# motor.net
KiCad netlist of a schematic drawn in EAGLE
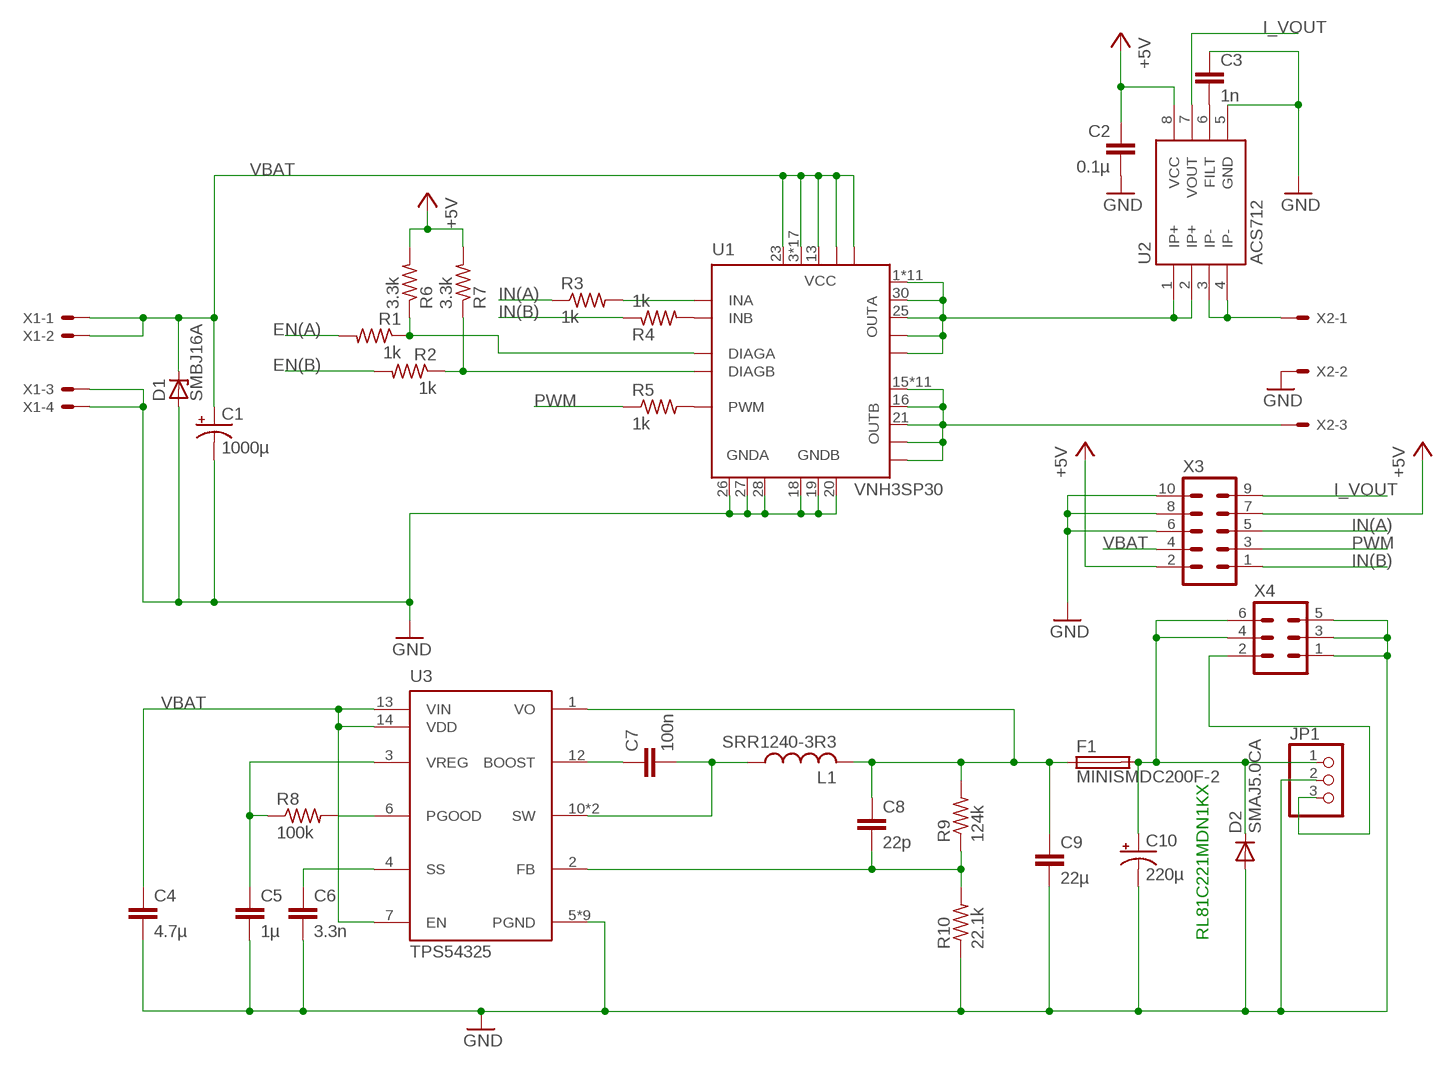
[diagram p0: schematic, sheet 1]

(export (version "E")
  (design (tool "Eeschema 10.0.6"))
  (components
    (comp (ref "C1")
      (value "1000µ")
      (footprint "eagle-import:E5-13")
      (libsource (lib "eagle-import") (part "CPOL-USE5-13"))
    )
    (comp (ref "C2")
      (value "0.1µ")
      (footprint "eagle-import:C0805")
      (libsource (lib "eagle-import") (part "C-EUC0805"))
    )
    (comp (ref "C3")
      (value "1n")
      (footprint "eagle-import:C0805")
      (libsource (lib "eagle-import") (part "C-EUC0805"))
    )
    (comp (ref "C4")
      (value "4.7µ")
      (footprint "eagle-import:C1206")
      (libsource (lib "eagle-import") (part "C-EUC1206"))
    )
    (comp (ref "C5")
      (value "1µ")
      (footprint "eagle-import:C0805")
      (libsource (lib "eagle-import") (part "C-EUC0805"))
    )
    (comp (ref "C6")
      (value "3.3n")
      (footprint "eagle-import:C0805")
      (libsource (lib "eagle-import") (part "C-EUC0805"))
    )
    (comp (ref "C7")
      (value "100n")
      (footprint "eagle-import:C0805")
      (libsource (lib "eagle-import") (part "C-EUC0805"))
    )
    (comp (ref "C8")
      (value "22p")
      (footprint "eagle-import:C0805")
      (libsource (lib "eagle-import") (part "C-EUC0805"))
    )
    (comp (ref "C9")
      (value "22µ")
      (footprint "eagle-import:C3225")
      (libsource (lib "eagle-import") (part "C-EUC3225"))
    )
    (comp (ref "C10")
      (value "220µ")
      (footprint "eagle-import:E3,5-8")
      (libsource (lib "eagle-import") (part "CPOL-USE3.5-8"))
    )
    (comp (ref "D1")
      (value "SMBJ16A")
      (footprint "eagle-import:SMB")
      (libsource (lib "eagle-import") (part "ZENER-DIODESMB"))
    )
    (comp (ref "D2")
      (value "SMAJ5.0CA")
      (footprint "eagle-import:DO-214AC")
      (libsource (lib "eagle-import") (part "DIODE-DO-214AC"))
    )
    (comp (ref "F1")
      (value "MINISMDC200F-2")
      (footprint "eagle-import:MINISMDC200F")
      (libsource (lib "eagle-import") (part "FUSEMINISMDC200F"))
    )
    (comp (ref "JP1")
      (value "PINHD-1X3")
      (footprint "eagle-import:1X03")
      (libsource (lib "eagle-import") (part "PINHD-1X3"))
    )
    (comp (ref "L1")
      (value "SRR1240-3R3")
      (footprint "eagle-import:HCM1103")
      (libsource (lib "eagle-import") (part "L-USHCM1103"))
    )
    (comp (ref "R1")
      (value "1k")
      (footprint "eagle-import:R0805")
      (libsource (lib "eagle-import") (part "R-US_R0805"))
    )
    (comp (ref "R2")
      (value "1k")
      (footprint "eagle-import:R0805")
      (libsource (lib "eagle-import") (part "R-US_R0805"))
    )
    (comp (ref "R3")
      (value "1k")
      (footprint "eagle-import:R0805")
      (libsource (lib "eagle-import") (part "R-US_R0805"))
    )
    (comp (ref "R4")
      (value "1k")
      (footprint "eagle-import:R0805")
      (libsource (lib "eagle-import") (part "R-US_R0805"))
    )
    (comp (ref "R5")
      (value "1k")
      (footprint "eagle-import:R0805")
      (libsource (lib "eagle-import") (part "R-US_R0805"))
    )
    (comp (ref "R6")
      (value "3.3k")
      (footprint "eagle-import:R0805")
      (libsource (lib "eagle-import") (part "R-US_R0805"))
    )
    (comp (ref "R7")
      (value "3.3k")
      (footprint "eagle-import:R0805")
      (libsource (lib "eagle-import") (part "R-US_R0805"))
    )
    (comp (ref "R8")
      (value "100k")
      (footprint "eagle-import:R0805")
      (libsource (lib "eagle-import") (part "R-US_R0805"))
    )
    (comp (ref "R9")
      (value "124k")
      (footprint "eagle-import:R0805")
      (libsource (lib "eagle-import") (part "R-US_R0805"))
    )
    (comp (ref "R10")
      (value "22.1k")
      (footprint "eagle-import:R0805")
      (libsource (lib "eagle-import") (part "R-US_R0805"))
    )
    (comp (ref "U1")
      (value "VNH3SP30")
      (footprint "eagle-import:MULTIPOWERSO-30")
      (fields (field (name "MPN") "VNH3SP30-E"))
      (libsource (lib "eagle-import") (part "VNH3SP30"))
    )
    (comp (ref "U2")
      (value "ACS712")
      (footprint "eagle-import:SO08")
      (libsource (lib "eagle-import") (part "ACS712"))
    )
    (comp (ref "U3")
      (value "TPS54325")
      (footprint "eagle-import:HTSSOP14PWP")
      (libsource (lib "eagle-import") (part "TPS54325"))
    )
    (comp (ref "X1")
      (value "KK-156-4")
      (footprint "eagle-import:KK-156-4")
      (libsource (lib "eagle-import") (part "KK-156-4"))
    )
    (comp (ref "X2")
      (value "KK-156-3")
      (footprint "eagle-import:KK-156-3")
      (libsource (lib "eagle-import") (part "KK-156-3"))
    )
    (comp (ref "X3")
      (value "ML10")
      (footprint "eagle-import:ML10")
      (libsource (lib "eagle-import") (part "ML10"))
    )
    (comp (ref "X4")
      (value "ML6")
      (footprint "eagle-import:ML6")
      (libsource (lib "eagle-import") (part "ML6"))
    )
  )
  (nets
    (net (code "1") (name "+5V") (class "Default")
      (node (ref "C2") (pin "1") (pinfunction "1_1") (pintype "passive"))
      (node (ref "R6") (pin "2") (pinfunction "2_2") (pintype "passive"))
      (node (ref "R7") (pin "2") (pinfunction "2_2") (pintype "passive"))
      (node (ref "U2") (pin "8") (pinfunction "VCC_8") (pintype "bidirectional"))
      (node (ref "X3") (pin "2") (pinfunction "2_2") (pintype "passive"))
      (node (ref "X3") (pin "7") (pinfunction "7_7") (pintype "passive"))
    )
    (net (code "2") (name "/EN(A)") (class "Default")
      (node (ref "R1") (pin "2") (pinfunction "2_2") (pintype "passive"))
    )
    (net (code "3") (name "/EN(B)") (class "Default")
      (node (ref "R2") (pin "2") (pinfunction "2_2") (pintype "passive"))
    )
    (net (code "4") (name "/IN(A)") (class "Default")
      (node (ref "R3") (pin "1") (pinfunction "1_1") (pintype "passive"))
      (node (ref "X3") (pin "5") (pinfunction "5_5") (pintype "passive"))
    )
    (net (code "5") (name "/IN(B)") (class "Default")
      (node (ref "R4") (pin "1") (pinfunction "1_1") (pintype "passive"))
      (node (ref "X3") (pin "1") (pinfunction "1_1") (pintype "passive"))
    )
    (net (code "6") (name "/I_VOUT") (class "Default")
      (node (ref "U2") (pin "7") (pinfunction "VOUT_7") (pintype "bidirectional"))
      (node (ref "X3") (pin "9") (pinfunction "9_9") (pintype "passive"))
    )
    (net (code "7") (name "/PWM") (class "Default")
      (node (ref "R5") (pin "1") (pinfunction "1_1") (pintype "passive"))
      (node (ref "X3") (pin "3") (pinfunction "3_3") (pintype "passive"))
    )
    (net (code "8") (name "/VBAT") (class "Default")
      (node (ref "C1") (pin "+") (pinfunction "+_+") (pintype "passive"))
      (node (ref "C4") (pin "1") (pinfunction "1_1") (pintype "passive"))
      (node (ref "D1") (pin "C") (pinfunction "C_C") (pintype "passive"))
      (node (ref "U1") (pin "13") (pinfunction "VCC_13") (pintype "power_in"))
      (node (ref "U1") (pin "23") (pinfunction "VCC_23") (pintype "power_in"))
      (node (ref "U1") (pin "3") (pinfunction "VCC_3") (pintype "power_in"))
      (node (ref "U1") (pin "VCC") (pinfunction "VCC_VCC") (pintype "power_in"))
      (node (ref "U1") (pin "VCC1") (pinfunction "VCC_VCC1") (pintype "power_in"))
      (node (ref "U1") (pin "VCC10") (pinfunction "VCC_VCC10") (pintype "power_in"))
      (node (ref "U1") (pin "VCC11") (pinfunction "VCC_VCC11") (pintype "power_in"))
      (node (ref "U1") (pin "VCC12") (pinfunction "VCC_VCC12") (pintype "power_in"))
      (node (ref "U1") (pin "VCC13") (pinfunction "VCC_VCC13") (pintype "power_in"))
      (node (ref "U1") (pin "VCC14") (pinfunction "VCC_VCC14") (pintype "power_in"))
      (node (ref "U1") (pin "VCC15") (pinfunction "VCC_VCC15") (pintype "power_in"))
      (node (ref "U1") (pin "VCC16") (pinfunction "VCC_VCC16") (pintype "power_in"))
      (node (ref "U1") (pin "VCC2") (pinfunction "VCC_VCC2") (pintype "power_in"))
      (node (ref "U1") (pin "VCC3") (pinfunction "VCC_VCC3") (pintype "power_in"))
      (node (ref "U1") (pin "VCC4") (pinfunction "VCC_VCC4") (pintype "power_in"))
      (node (ref "U1") (pin "VCC5") (pinfunction "VCC_VCC5") (pintype "power_in"))
      (node (ref "U1") (pin "VCC6") (pinfunction "VCC_VCC6") (pintype "power_in"))
      (node (ref "U1") (pin "VCC7") (pinfunction "VCC_VCC7") (pintype "power_in"))
      (node (ref "U1") (pin "VCC8") (pinfunction "VCC_VCC8") (pintype "power_in"))
      (node (ref "U1") (pin "VCC9") (pinfunction "VCC_VCC9") (pintype "power_in"))
      (node (ref "U1") (pin "VCC@1") (pinfunction "VCC_VCC@1") (pintype "power_in"))
      (node (ref "U3") (pin "13") (pinfunction "VIN_13") (pintype "bidirectional"))
      (node (ref "U3") (pin "14") (pinfunction "VDD_14") (pintype "bidirectional"))
      (node (ref "U3") (pin "7") (pinfunction "EN_7") (pintype "bidirectional"))
      (node (ref "X1") (pin "1") (pinfunction "S_1") (pintype "passive"))
      (node (ref "X1") (pin "2") (pinfunction "S_2") (pintype "passive"))
      (node (ref "X3") (pin "4") (pinfunction "4_4") (pintype "passive"))
    )
    (net (code "9") (name "GND") (class "Default")
      (node (ref "C1") (pin "-") (pinfunction "-_-") (pintype "passive"))
      (node (ref "C10") (pin "-") (pinfunction "-_-") (pintype "passive"))
      (node (ref "C2") (pin "2") (pinfunction "2_2") (pintype "passive"))
      (node (ref "C3") (pin "1") (pinfunction "1_1") (pintype "passive"))
      (node (ref "C4") (pin "2") (pinfunction "2_2") (pintype "passive"))
      (node (ref "C5") (pin "2") (pinfunction "2_2") (pintype "passive"))
      (node (ref "C6") (pin "2") (pinfunction "2_2") (pintype "passive"))
      (node (ref "C9") (pin "2") (pinfunction "2_2") (pintype "passive"))
      (node (ref "D1") (pin "A") (pinfunction "A_A") (pintype "passive"))
      (node (ref "D2") (pin "A") (pinfunction "A_A") (pintype "passive"))
      (node (ref "JP1") (pin "2") (pinfunction "2_2") (pintype "passive"))
      (node (ref "R10") (pin "1") (pinfunction "1_1") (pintype "passive"))
      (node (ref "U1") (pin "18") (pinfunction "GNDB_18") (pintype "power_in"))
      (node (ref "U1") (pin "19") (pinfunction "GNDB_19") (pintype "power_in"))
      (node (ref "U1") (pin "20") (pinfunction "GNDB_20") (pintype "power_in"))
      (node (ref "U1") (pin "26") (pinfunction "GNDA_26") (pintype "power_in"))
      (node (ref "U1") (pin "27") (pinfunction "GNDA_27") (pintype "power_in"))
      (node (ref "U1") (pin "28") (pinfunction "GNDA_28") (pintype "power_in"))
      (node (ref "U2") (pin "5") (pinfunction "GND_5") (pintype "bidirectional"))
      (node (ref "U3") (pin "5") (pinfunction "PGND_5") (pintype "bidirectional"))
      (node (ref "U3") (pin "8") (pinfunction "PGND_8") (pintype "bidirectional"))
      (node (ref "U3") (pin "9") (pinfunction "PGND_9") (pintype "bidirectional"))
      (node (ref "U3") (pin "EXP") (pinfunction "PGND_EXP") (pintype "bidirectional"))
      (node (ref "U3") (pin "EXP1") (pinfunction "PGND_EXP1") (pintype "bidirectional"))
      (node (ref "U3") (pin "P$1") (pinfunction "PGND_P$1") (pintype "bidirectional"))
      (node (ref "U3") (pin "P$2") (pinfunction "PGND_P$2") (pintype "bidirectional"))
      (node (ref "U3") (pin "P$3") (pinfunction "PGND_P$3") (pintype "bidirectional"))
      (node (ref "U3") (pin "P$4") (pinfunction "PGND_P$4") (pintype "bidirectional"))
      (node (ref "X1") (pin "3") (pinfunction "S_3") (pintype "passive"))
      (node (ref "X1") (pin "4") (pinfunction "S_4") (pintype "passive"))
      (node (ref "X2") (pin "2") (pinfunction "S_2") (pintype "passive"))
      (node (ref "X3") (pin "10") (pinfunction "10_10") (pintype "passive"))
      (node (ref "X3") (pin "6") (pinfunction "6_6") (pintype "passive"))
      (node (ref "X3") (pin "8") (pinfunction "8_8") (pintype "passive"))
      (node (ref "X4") (pin "1") (pinfunction "1_1") (pintype "passive"))
      (node (ref "X4") (pin "3") (pinfunction "3_3") (pintype "passive"))
      (node (ref "X4") (pin "5") (pinfunction "5_5") (pintype "passive"))
    )
    (net (code "10") (name "Net-(C10-Pad+)") (class "Default")
      (node (ref "C10") (pin "+") (pinfunction "+_+") (pintype "passive"))
      (node (ref "D2") (pin "C") (pinfunction "C_C") (pintype "passive"))
      (node (ref "F1") (pin "2") (pinfunction "2_2") (pintype "passive"))
      (node (ref "JP1") (pin "1") (pinfunction "1_1") (pintype "passive"))
      (node (ref "X4") (pin "4") (pinfunction "4_4") (pintype "passive"))
      (node (ref "X4") (pin "6") (pinfunction "6_6") (pintype "passive"))
    )
    (net (code "11") (name "Net-(JP1-Pad3)") (class "Default")
      (node (ref "JP1") (pin "3") (pinfunction "3_3") (pintype "passive"))
      (node (ref "X4") (pin "2") (pinfunction "2_2") (pintype "passive"))
    )
    (net (code "12") (name "Net-(L1-1)") (class "Default")
      (node (ref "C7") (pin "2") (pinfunction "2_2") (pintype "passive"))
      (node (ref "L1") (pin "P$1") (pinfunction "1_P$1") (pintype "passive"))
      (node (ref "U3") (pin "10") (pinfunction "SW_10") (pintype "bidirectional"))
      (node (ref "U3") (pin "11") (pinfunction "SW_11") (pintype "bidirectional"))
    )
    (net (code "13") (name "Net-(L1-2)") (class "Default")
      (node (ref "C8") (pin "1") (pinfunction "1_1") (pintype "passive"))
      (node (ref "C9") (pin "1") (pinfunction "1_1") (pintype "passive"))
      (node (ref "F1") (pin "1") (pinfunction "1_1") (pintype "passive"))
      (node (ref "L1") (pin "P$2") (pinfunction "2_P$2") (pintype "passive"))
      (node (ref "R9") (pin "2") (pinfunction "2_2") (pintype "passive"))
      (node (ref "U3") (pin "1") (pinfunction "VO_1") (pintype "bidirectional"))
    )
    (net (code "14") (name "Net-(U1-DIAGA)") (class "Default")
      (node (ref "R1") (pin "1") (pinfunction "1_1") (pintype "passive"))
      (node (ref "R6") (pin "1") (pinfunction "1_1") (pintype "passive"))
      (node (ref "U1") (pin "6") (pinfunction "DIAGA_6") (pintype "open_collector"))
    )
    (net (code "15") (name "Net-(U1-DIAGB)") (class "Default")
      (node (ref "R2") (pin "1") (pinfunction "1_1") (pintype "passive"))
      (node (ref "R7") (pin "1") (pinfunction "1_1") (pintype "passive"))
      (node (ref "U1") (pin "10") (pinfunction "DIAGB_10") (pintype "open_collector"))
    )
    (net (code "16") (name "Net-(U1-INA)") (class "Default")
      (node (ref "R3") (pin "2") (pinfunction "2_2") (pintype "passive"))
      (node (ref "U1") (pin "5") (pinfunction "INA_5") (pintype "input"))
    )
    (net (code "17") (name "Net-(U1-INB)") (class "Default")
      (node (ref "R4") (pin "2") (pinfunction "2_2") (pintype "passive"))
      (node (ref "U1") (pin "11") (pinfunction "INB_11") (pintype "input"))
    )
    (net (code "18") (name "Net-(U1-OUTA-Pad1)") (class "Default")
      (node (ref "U1") (pin "1") (pinfunction "OUTA_1") (pintype "output"))
      (node (ref "U1") (pin "25") (pinfunction "OUTA_25") (pintype "passive"))
      (node (ref "U1") (pin "30") (pinfunction "OUTA_30") (pintype "passive"))
      (node (ref "U1") (pin "OUTA") (pinfunction "OUTA_OUTA") (pintype "passive"))
      (node (ref "U1") (pin "OUTA1") (pinfunction "OUTA_OUTA1") (pintype "output"))
      (node (ref "U1") (pin "OUTA10") (pinfunction "OUTA_OUTA10") (pintype "output"))
      (node (ref "U1") (pin "OUTA2") (pinfunction "OUTA_OUTA2") (pintype "output"))
      (node (ref "U1") (pin "OUTA3") (pinfunction "OUTA_OUTA3") (pintype "output"))
      (node (ref "U1") (pin "OUTA4") (pinfunction "OUTA_OUTA4") (pintype "output"))
      (node (ref "U1") (pin "OUTA5") (pinfunction "OUTA_OUTA5") (pintype "output"))
      (node (ref "U1") (pin "OUTA6") (pinfunction "OUTA_OUTA6") (pintype "output"))
      (node (ref "U1") (pin "OUTA7") (pinfunction "OUTA_OUTA7") (pintype "output"))
      (node (ref "U1") (pin "OUTA8") (pinfunction "OUTA_OUTA8") (pintype "output"))
      (node (ref "U1") (pin "OUTA9") (pinfunction "OUTA_OUTA9") (pintype "output"))
      (node (ref "U1") (pin "OUTA@1") (pinfunction "OUTA_OUTA@1") (pintype "passive"))
      (node (ref "U2") (pin "1") (pinfunction "IP+_1") (pintype "bidirectional"))
      (node (ref "U2") (pin "2") (pinfunction "IP+_2") (pintype "bidirectional"))
    )
    (net (code "19") (name "Net-(U1-PWM)") (class "Default")
      (node (ref "R5") (pin "2") (pinfunction "2_2") (pintype "passive"))
      (node (ref "U1") (pin "8") (pinfunction "PWM_8") (pintype "input"))
    )
    (net (code "20") (name "Net-(U2-FILT)") (class "Default")
      (node (ref "C3") (pin "2") (pinfunction "2_2") (pintype "passive"))
      (node (ref "U2") (pin "6") (pinfunction "FILT_6") (pintype "bidirectional"))
    )
    (net (code "21") (name "Net-(U3-BOOST)") (class "Default")
      (node (ref "C7") (pin "1") (pinfunction "1_1") (pintype "passive"))
      (node (ref "U3") (pin "12") (pinfunction "BOOST_12") (pintype "bidirectional"))
    )
    (net (code "22") (name "Net-(U3-FB)") (class "Default")
      (node (ref "C8") (pin "2") (pinfunction "2_2") (pintype "passive"))
      (node (ref "R10") (pin "2") (pinfunction "2_2") (pintype "passive"))
      (node (ref "R9") (pin "1") (pinfunction "1_1") (pintype "passive"))
      (node (ref "U3") (pin "2") (pinfunction "FB_2") (pintype "bidirectional"))
    )
    (net (code "23") (name "Net-(U3-PGOOD)") (class "Default")
      (node (ref "R8") (pin "2") (pinfunction "2_2") (pintype "passive"))
      (node (ref "U3") (pin "6") (pinfunction "PGOOD_6") (pintype "bidirectional"))
    )
    (net (code "24") (name "Net-(U3-SS)") (class "Default")
      (node (ref "C6") (pin "1") (pinfunction "1_1") (pintype "passive"))
      (node (ref "U3") (pin "4") (pinfunction "SS_4") (pintype "bidirectional"))
    )
    (net (code "25") (name "Net-(U3-VREG)") (class "Default")
      (node (ref "C5") (pin "1") (pinfunction "1_1") (pintype "passive"))
      (node (ref "R8") (pin "1") (pinfunction "1_1") (pintype "passive"))
      (node (ref "U3") (pin "3") (pinfunction "VREG_3") (pintype "bidirectional"))
    )
    (net (code "26") (name "Net-(X2A-S)") (class "Default")
      (node (ref "U2") (pin "3") (pinfunction "IP-_3") (pintype "bidirectional"))
      (node (ref "U2") (pin "4") (pinfunction "IP-_4") (pintype "bidirectional"))
      (node (ref "X2") (pin "1") (pinfunction "S_1") (pintype "passive"))
    )
    (net (code "27") (name "Net-(X2C-S)") (class "Default")
      (node (ref "U1") (pin "15") (pinfunction "OUTB_15") (pintype "output"))
      (node (ref "U1") (pin "16") (pinfunction "OUTB_16") (pintype "passive"))
      (node (ref "U1") (pin "21") (pinfunction "OUTB_21") (pintype "passive"))
      (node (ref "U1") (pin "OUTB") (pinfunction "OUTB_OUTB") (pintype "passive"))
      (node (ref "U1") (pin "OUTB1") (pinfunction "OUTB_OUTB1") (pintype "output"))
      (node (ref "U1") (pin "OUTB10") (pinfunction "OUTB_OUTB10") (pintype "output"))
      (node (ref "U1") (pin "OUTB2") (pinfunction "OUTB_OUTB2") (pintype "output"))
      (node (ref "U1") (pin "OUTB3") (pinfunction "OUTB_OUTB3") (pintype "output"))
      (node (ref "U1") (pin "OUTB4") (pinfunction "OUTB_OUTB4") (pintype "output"))
      (node (ref "U1") (pin "OUTB5") (pinfunction "OUTB_OUTB5") (pintype "output"))
      (node (ref "U1") (pin "OUTB6") (pinfunction "OUTB_OUTB6") (pintype "output"))
      (node (ref "U1") (pin "OUTB7") (pinfunction "OUTB_OUTB7") (pintype "output"))
      (node (ref "U1") (pin "OUTB8") (pinfunction "OUTB_OUTB8") (pintype "output"))
      (node (ref "U1") (pin "OUTB9") (pinfunction "OUTB_OUTB9") (pintype "output"))
      (node (ref "U1") (pin "OUTB@1") (pinfunction "OUTB_OUTB@1") (pintype "passive"))
      (node (ref "X2") (pin "3") (pinfunction "S_3") (pintype "passive"))
    )
  )
)
